# Voltage_Controlled_Oscillator.net
KiCad netlist of a schematic drawn in Altium Designer
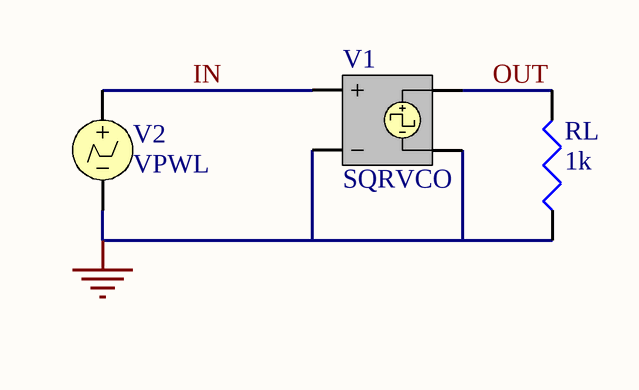
[diagram p0: Voltage Controlled Oscillator.schdoc]

(export (version "E")
  (design (tool "Eeschema 10.0.6"))
  (components
    (comp (ref "RL") (value "1k") (description "Resistor") (libsource (lib "*") (part "RES")))
    (comp (ref "V1")
      (value "SQRVCO")
      (description "Square Voltage Controlled Oscillator")
      (libsource (lib "*") (part "SQRVCO"))
    )
    (comp (ref "V2")
      (value "VPWL")
      (description "Piecewise Linear Voltage Source")
      (libsource (lib "*") (part "VPWL"))
    )
  )
  (nets
    (net (code "1") (name "/IN") (class "Default")
      (node (ref "V1") (pin "1") (pinfunction "NC+_1") (pintype "passive"))
      (node (ref "V2") (pin "1") (pinfunction "1_1") (pintype "passive"))
    )
    (net (code "2") (name "/OUT") (class "Default")
      (node (ref "RL") (pin "1") (pinfunction "TOP_1") (pintype "passive"))
      (node (ref "V1") (pin "3") (pinfunction "N+_3") (pintype "passive"))
    )
    (net (code "3") (name "GND") (class "Default")
      (node (ref "RL") (pin "2") (pinfunction "BOT_2") (pintype "passive"))
      (node (ref "V1") (pin "2") (pinfunction "NC-_2") (pintype "passive"))
      (node (ref "V1") (pin "4") (pinfunction "N-_4") (pintype "passive"))
      (node (ref "V2") (pin "2") (pinfunction "2_2") (pintype "passive"))
    )
  )
)
